# Headers.net
KiCad netlist of a schematic drawn in Altium Designer
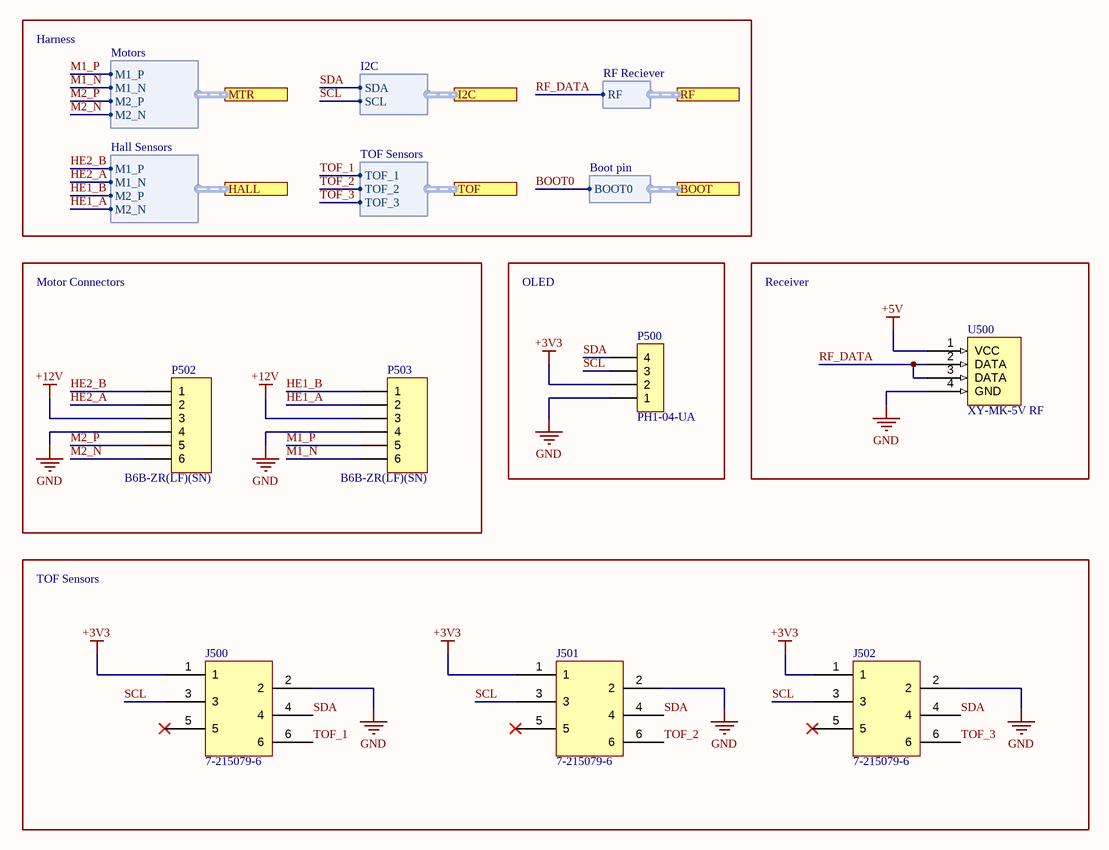
[diagram p0: Headers.SchDoc]

(export (version "E")
  (design (tool "Eeschema 10.0.6"))
  (components
    (comp (ref "J500")
      (value "7-215079-6")
      (footprint "7-215079-6-Footprint-1")
      (description "Conn FFC Connector F 6 POS 1.27mm Solder ST Thru-Hole Automotive Box/Carton")
      (fields (field (name "MANUFACTURER") "TE Connectivity"))
      (libsource (lib "Krakul Vault") (part "7-215079-6"))
    )
    (comp (ref "J501")
      (value "7-215079-6")
      (footprint "7-215079-6-Footprint-1")
      (description "Conn FFC Connector F 6 POS 1.27mm Solder ST Thru-Hole Automotive Box/Carton")
      (fields (field (name "MANUFACTURER") "TE Connectivity"))
      (libsource (lib "Krakul Vault") (part "7-215079-6"))
    )
    (comp (ref "J502")
      (value "7-215079-6")
      (footprint "7-215079-6-Footprint-1")
      (description "Conn FFC Connector F 6 POS 1.27mm Solder ST Thru-Hole Automotive Box/Carton")
      (fields (field (name "MANUFACTURER") "TE Connectivity"))
      (libsource (lib "Krakul Vault") (part "7-215079-6"))
    )
    (comp (ref "P500")
      (value "PH1-04-UA")
      (footprint "4Pos Pin Header Vertical")
      (description "4 POS 2.54mm Vertical THT Header")
      (fields (field (name "MANUFACTURER") "Adam Tech"))
      (libsource (lib "Krakul Vault") (part "4POS GENERIC"))
    )
    (comp (ref "P502")
      (value "B6B-ZR(LF)(SN)")
      (footprint "FP-B6B-ZR-SM4-TF_LF_SN-MFG")
      (description "Header for PCB; pitch 1.50mm; 6-contacts; THT; male; top entry; 50V/1A")
      (fields (field (name "MANUFACTURER") "JST Sales America Inc.") (field (name "PART NUMBER") "B6B-ZR"))
      (libsource (lib "Krakul Vault") (part "6 pin header"))
    )
    (comp (ref "P503")
      (value "B6B-ZR(LF)(SN)")
      (footprint "FP-B6B-ZR-SM4-TF_LF_SN-MFG")
      (description "Header for PCB; pitch 1.50mm; 6-contacts; THT; male; top entry; 50V/1A")
      (fields (field (name "MANUFACTURER") "JST Sales America Inc.") (field (name "PART NUMBER") "B6B-ZR"))
      (libsource (lib "Krakul Vault") (part "6 pin header"))
    )
    (comp (ref "U500")
      (value "XY-MK-5V RF")
      (footprint "2.54mm 4 POS XY-MK-5V RF")
      (description "433MHz reciever module, 5V tolerant")
      (fields (field (name "MANUFACTURER") "Unknown"))
      (libsource (lib "Krakul Vault") (part "XY-MK-5V RF-Symbol-1"))
    )
  )
  (nets
    (net (code "10") (name "+3V3") (class "Default")
      (node (ref "J500") (pin "1") (pinfunction "1_1") (pintype "passive"))
      (node (ref "J501") (pin "1") (pinfunction "1_1") (pintype "passive"))
      (node (ref "J502") (pin "1") (pinfunction "1_1") (pintype "passive"))
      (node (ref "P500") (pin "2") (pinfunction "2_2") (pintype "passive"))
    )
    (net (code "11") (name "+5V") (class "Default")
      (node (ref "U500") (pin "1") (pinfunction "VCC_1") (pintype "input"))
    )
    (net (code "12") (name "+12V") (class "Default")
      (node (ref "P502") (pin "3") (pinfunction "3_3") (pintype "passive"))
      (node (ref "P503") (pin "3") (pinfunction "3_3") (pintype "passive"))
    )
    (net (code "14") (name "/HE1_A") (class "Default")
      (node (ref "P503") (pin "2") (pinfunction "2_2") (pintype "passive"))
    )
    (net (code "15") (name "/HE1_B") (class "Default")
      (node (ref "P503") (pin "1") (pinfunction "1_1") (pintype "passive"))
    )
    (net (code "16") (name "/HE2_A") (class "Default")
      (node (ref "P502") (pin "2") (pinfunction "2_2") (pintype "passive"))
    )
    (net (code "17") (name "/HE2_B") (class "Default")
      (node (ref "P502") (pin "1") (pinfunction "1_1") (pintype "passive"))
    )
    (net (code "18") (name "/M1_N") (class "Default")
      (node (ref "P503") (pin "6") (pinfunction "6_6") (pintype "passive"))
    )
    (net (code "19") (name "/M1_P") (class "Default")
      (node (ref "P503") (pin "5") (pinfunction "5_5") (pintype "passive"))
    )
    (net (code "20") (name "/M2_N") (class "Default")
      (node (ref "P502") (pin "6") (pinfunction "6_6") (pintype "passive"))
    )
    (net (code "21") (name "/M2_P") (class "Default")
      (node (ref "P502") (pin "5") (pinfunction "5_5") (pintype "passive"))
    )
    (net (code "22") (name "/RF_DATA") (class "Default")
      (node (ref "U500") (pin "2") (pinfunction "DATA_2") (pintype "input"))
      (node (ref "U500") (pin "3") (pinfunction "DATA_3") (pintype "input"))
    )
    (net (code "23") (name "/SCL") (class "Default")
      (node (ref "J500") (pin "3") (pinfunction "3_3") (pintype "passive"))
      (node (ref "J501") (pin "3") (pinfunction "3_3") (pintype "passive"))
      (node (ref "J502") (pin "3") (pinfunction "3_3") (pintype "passive"))
      (node (ref "P500") (pin "3") (pinfunction "3_3") (pintype "passive"))
    )
    (net (code "24") (name "/SDA") (class "Default")
      (node (ref "J500") (pin "4") (pinfunction "4_4") (pintype "passive"))
      (node (ref "J501") (pin "4") (pinfunction "4_4") (pintype "passive"))
      (node (ref "J502") (pin "4") (pinfunction "4_4") (pintype "passive"))
      (node (ref "P500") (pin "4") (pinfunction "4_4") (pintype "passive"))
    )
    (net (code "25") (name "/TOF_1") (class "Default")
      (node (ref "J500") (pin "6") (pinfunction "6_6") (pintype "passive"))
    )
    (net (code "26") (name "/TOF_2") (class "Default")
      (node (ref "J501") (pin "6") (pinfunction "6_6") (pintype "passive"))
    )
    (net (code "27") (name "/TOF_3") (class "Default")
      (node (ref "J502") (pin "6") (pinfunction "6_6") (pintype "passive"))
    )
    (net (code "34") (name "GND") (class "Default")
      (node (ref "J500") (pin "2") (pinfunction "2_2") (pintype "passive"))
      (node (ref "J501") (pin "2") (pinfunction "2_2") (pintype "passive"))
      (node (ref "J502") (pin "2") (pinfunction "2_2") (pintype "passive"))
      (node (ref "P500") (pin "1") (pinfunction "1_1") (pintype "passive"))
      (node (ref "P502") (pin "4") (pinfunction "4_4") (pintype "passive"))
      (node (ref "P503") (pin "4") (pinfunction "4_4") (pintype "passive"))
      (node (ref "U500") (pin "4") (pinfunction "GND_4") (pintype "input"))
    )
    (net (code "35") (name "unconnected-(J500-Pad5)") (class "Default")
      (node (ref "J500") (pin "5") (pinfunction "5_5") (pintype "passive+no_connect"))
    )
    (net (code "36") (name "unconnected-(J501-Pad5)") (class "Default")
      (node (ref "J501") (pin "5") (pinfunction "5_5") (pintype "passive+no_connect"))
    )
    (net (code "37") (name "unconnected-(J502-Pad5)") (class "Default")
      (node (ref "J502") (pin "5") (pinfunction "5_5") (pintype "passive+no_connect"))
    )
  )
)
